# CarteTxCapteurDistance.net
KiCad netlist of a schematic drawn in Altium Designer
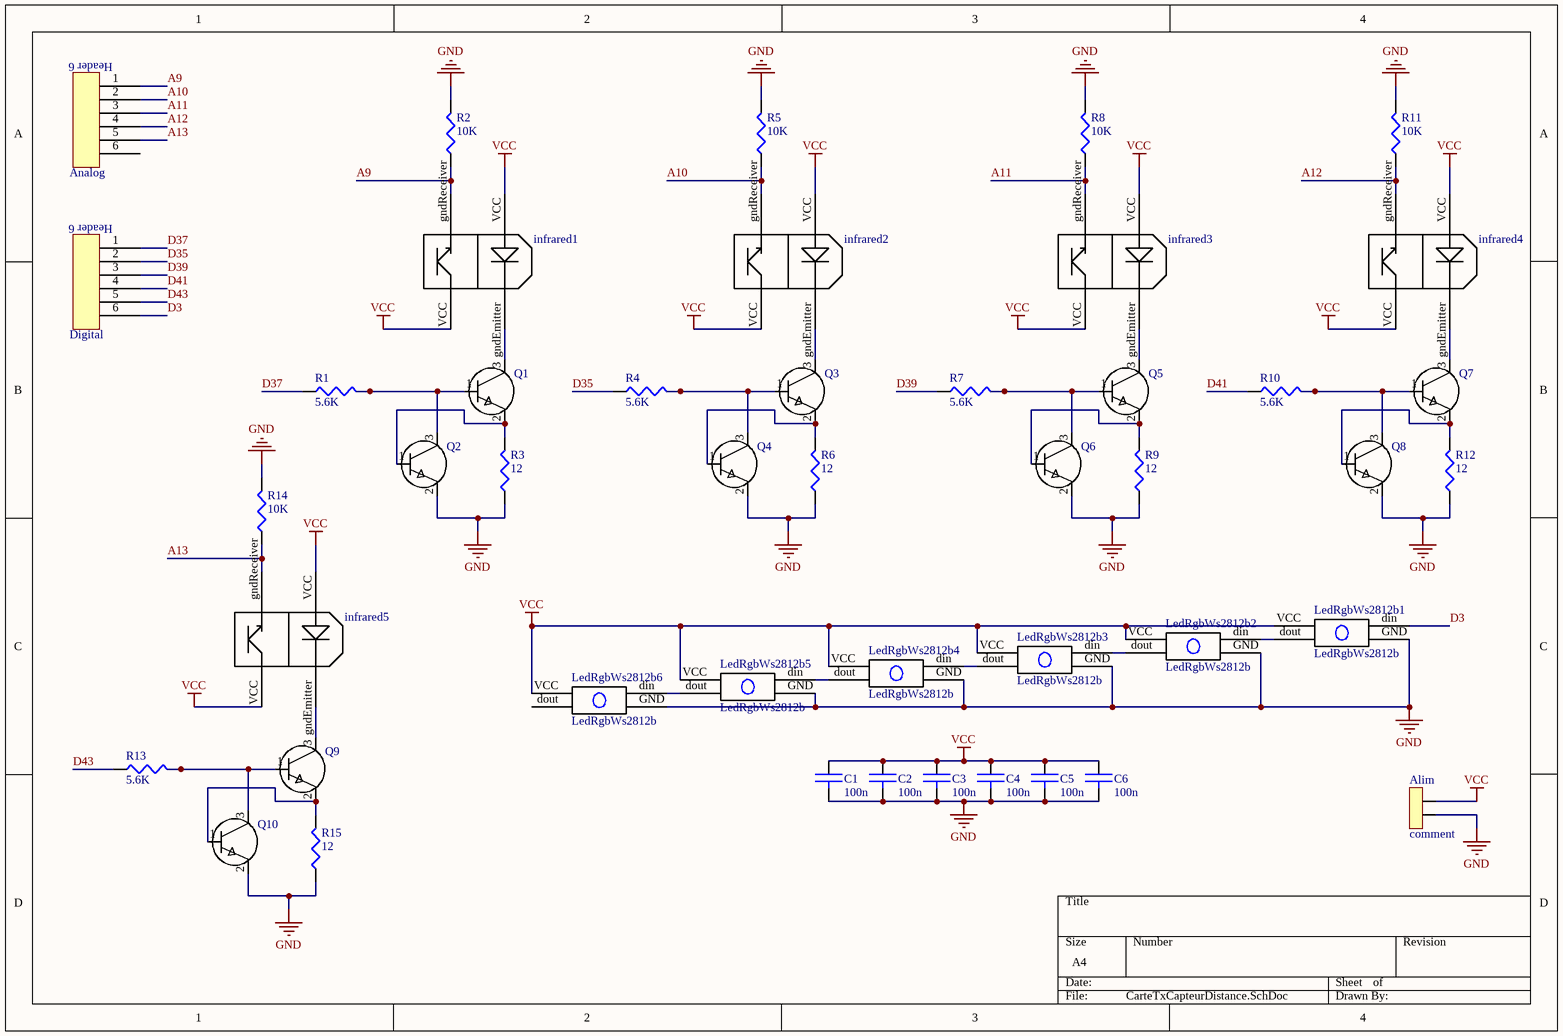
[diagram p0: CarteTxCapteurDistance.SchDoc]

(export (version "E")
  (design (tool "Eeschema 10.0.6"))
  (components
    (comp (ref "Alim")
      (value "comment")
      (footprint "POWER2")
      (description "connecteur alim 2 pôles")
      (libsource (lib "ISEN_basics_26-05-2015") (part "POWER2"))
    )
    (comp (ref "Analog")
      (value "Analog")
      (footprint "HEADER6")
      (libsource (lib "ledBitsLibrary") (part "HEADER6"))
    )
    (comp (ref "C1")
      (value "100n")
      (footprint "0805")
      (description "capacité non polarisée")
      (fields (field (name "Comment") "CAP"))
      (libsource (lib "ISEN_basics_26-05-2015") (part "CAP"))
    )
    (comp (ref "C2")
      (value "100n")
      (footprint "0805")
      (description "capacité non polarisée")
      (fields (field (name "Comment") "CAP"))
      (libsource (lib "ISEN_basics_26-05-2015") (part "CAP"))
    )
    (comp (ref "C3")
      (value "100n")
      (footprint "0805")
      (description "capacité non polarisée")
      (fields (field (name "Comment") "CAP"))
      (libsource (lib "ISEN_basics_26-05-2015") (part "CAP"))
    )
    (comp (ref "C4")
      (value "100n")
      (footprint "0805")
      (description "capacité non polarisée")
      (fields (field (name "Comment") "CAP"))
      (libsource (lib "ISEN_basics_26-05-2015") (part "CAP"))
    )
    (comp (ref "C5")
      (value "100n")
      (footprint "0805")
      (description "capacité non polarisée")
      (fields (field (name "Comment") "CAP"))
      (libsource (lib "ISEN_basics_26-05-2015") (part "CAP"))
    )
    (comp (ref "C6")
      (value "100n")
      (footprint "0805")
      (description "capacité non polarisée")
      (fields (field (name "Comment") "CAP"))
      (libsource (lib "ISEN_basics_26-05-2015") (part "CAP"))
    )
    (comp (ref "Digital")
      (value "Digital")
      (footprint "HEADER6")
      (libsource (lib "ledBitsLibrary") (part "HEADER6"))
    )
    (comp (ref "infrared1")
      (value "infrared")
      (footprint "Infrared")
      (libsource (lib "SecondLibrary") (part "RPR-359F"))
    )
    (comp (ref "infrared2")
      (value "infrared")
      (footprint "Infrared")
      (libsource (lib "SecondLibrary") (part "RPR-359F"))
    )
    (comp (ref "infrared3")
      (value "infrared")
      (footprint "Infrared")
      (libsource (lib "SecondLibrary") (part "RPR-359F"))
    )
    (comp (ref "infrared4")
      (value "infrared")
      (footprint "Infrared")
      (libsource (lib "SecondLibrary") (part "RPR-359F"))
    )
    (comp (ref "infrared5")
      (value "infrared")
      (footprint "Infrared")
      (libsource (lib "SecondLibrary") (part "RPR-359F"))
    )
    (comp (ref "LedRgbWs2812b1")
      (value "LedRgbWs2812b")
      (footprint "LedRgbWs2812b")
      (libsource (lib "SecondLibrary") (part "LedRgbWs2812b"))
    )
    (comp (ref "LedRgbWs2812b2")
      (value "LedRgbWs2812b")
      (footprint "LedRgbWs2812b")
      (libsource (lib "SecondLibrary") (part "LedRgbWs2812b"))
    )
    (comp (ref "LedRgbWs2812b3")
      (value "LedRgbWs2812b")
      (footprint "LedRgbWs2812b")
      (libsource (lib "SecondLibrary") (part "LedRgbWs2812b"))
    )
    (comp (ref "LedRgbWs2812b4")
      (value "LedRgbWs2812b")
      (footprint "LedRgbWs2812b")
      (libsource (lib "SecondLibrary") (part "LedRgbWs2812b"))
    )
    (comp (ref "LedRgbWs2812b5")
      (value "LedRgbWs2812b")
      (footprint "LedRgbWs2812b")
      (libsource (lib "SecondLibrary") (part "LedRgbWs2812b"))
    )
    (comp (ref "LedRgbWs2812b6")
      (value "LedRgbWs2812b")
      (footprint "LedRgbWs2812b")
      (libsource (lib "SecondLibrary") (part "LedRgbWs2812b"))
    )
    (comp (ref "Q1")
      (value "Q1")
      (footprint "BC817-40")
      (libsource (lib "SecondLibrary") (part "Transistors"))
    )
    (comp (ref "Q2")
      (value "Q2")
      (footprint "BC817-40")
      (libsource (lib "SecondLibrary") (part "Transistors"))
    )
    (comp (ref "Q3")
      (value "Q1")
      (footprint "BC817-40")
      (libsource (lib "SecondLibrary") (part "Transistors"))
    )
    (comp (ref "Q4")
      (value "Q2")
      (footprint "BC817-40")
      (libsource (lib "SecondLibrary") (part "Transistors"))
    )
    (comp (ref "Q5")
      (value "Q1")
      (footprint "BC817-40")
      (libsource (lib "SecondLibrary") (part "Transistors"))
    )
    (comp (ref "Q6")
      (value "Q2")
      (footprint "BC817-40")
      (libsource (lib "SecondLibrary") (part "Transistors"))
    )
    (comp (ref "Q7")
      (value "Q1")
      (footprint "BC817-40")
      (libsource (lib "SecondLibrary") (part "Transistors"))
    )
    (comp (ref "Q8")
      (value "Q2")
      (footprint "BC817-40")
      (libsource (lib "SecondLibrary") (part "Transistors"))
    )
    (comp (ref "Q9")
      (value "Q1")
      (footprint "BC817-40")
      (libsource (lib "SecondLibrary") (part "Transistors"))
    )
    (comp (ref "Q10")
      (value "Q2")
      (footprint "BC817-40")
      (libsource (lib "SecondLibrary") (part "Transistors"))
    )
    (comp (ref "R1")
      (value "5.6K")
      (footprint "0805")
      (description "resistance")
      (fields (field (name "Comment") "RES"))
      (libsource (lib "ISEN_basics_26-05-2015") (part "RES"))
    )
    (comp (ref "R2")
      (value "10K")
      (footprint "0805")
      (description "resistance")
      (fields (field (name "Comment") "RES"))
      (libsource (lib "ISEN_basics_26-05-2015") (part "RES"))
    )
    (comp (ref "R3")
      (value "12")
      (footprint "0805")
      (description "resistance")
      (fields (field (name "Comment") "RES"))
      (libsource (lib "ISEN_basics_26-05-2015") (part "RES"))
    )
    (comp (ref "R4")
      (value "5.6K")
      (footprint "0805")
      (description "resistance")
      (fields (field (name "Comment") "RES"))
      (libsource (lib "ISEN_basics_26-05-2015") (part "RES"))
    )
    (comp (ref "R5")
      (value "10K")
      (footprint "0805")
      (description "resistance")
      (fields (field (name "Comment") "RES"))
      (libsource (lib "ISEN_basics_26-05-2015") (part "RES"))
    )
    (comp (ref "R6")
      (value "12")
      (footprint "0805")
      (description "resistance")
      (fields (field (name "Comment") "RES"))
      (libsource (lib "ISEN_basics_26-05-2015") (part "RES"))
    )
    (comp (ref "R7")
      (value "5.6K")
      (footprint "0805")
      (description "resistance")
      (fields (field (name "Comment") "RES"))
      (libsource (lib "ISEN_basics_26-05-2015") (part "RES"))
    )
    (comp (ref "R8")
      (value "10K")
      (footprint "0805")
      (description "resistance")
      (fields (field (name "Comment") "RES"))
      (libsource (lib "ISEN_basics_26-05-2015") (part "RES"))
    )
    (comp (ref "R9")
      (value "12")
      (footprint "0805")
      (description "resistance")
      (fields (field (name "Comment") "RES"))
      (libsource (lib "ISEN_basics_26-05-2015") (part "RES"))
    )
    (comp (ref "R10")
      (value "5.6K")
      (footprint "0805")
      (description "resistance")
      (fields (field (name "Comment") "RES"))
      (libsource (lib "ISEN_basics_26-05-2015") (part "RES"))
    )
    (comp (ref "R11")
      (value "10K")
      (footprint "0805")
      (description "resistance")
      (fields (field (name "Comment") "RES"))
      (libsource (lib "ISEN_basics_26-05-2015") (part "RES"))
    )
    (comp (ref "R12")
      (value "12")
      (footprint "0805")
      (description "resistance")
      (fields (field (name "Comment") "RES"))
      (libsource (lib "ISEN_basics_26-05-2015") (part "RES"))
    )
    (comp (ref "R13")
      (value "5.6K")
      (footprint "0805")
      (description "resistance")
      (fields (field (name "Comment") "RES"))
      (libsource (lib "ISEN_basics_26-05-2015") (part "RES"))
    )
    (comp (ref "R14")
      (value "10K")
      (footprint "0805")
      (description "resistance")
      (fields (field (name "Comment") "RES"))
      (libsource (lib "ISEN_basics_26-05-2015") (part "RES"))
    )
    (comp (ref "R15")
      (value "12")
      (footprint "0805")
      (description "resistance")
      (fields (field (name "Comment") "RES"))
      (libsource (lib "ISEN_basics_26-05-2015") (part "RES"))
    )
  )
  (nets
    (net (code "1") (name "/A9") (class "Default")
      (node (ref "Analog") (pin "1") (pinfunction "1_1") (pintype "passive"))
      (node (ref "R2") (pin "1") (pintype "passive"))
      (node (ref "infrared1") (pin "gndReceiver") (pinfunction "gndReceiver_gndReceiver") (pintype "passive"))
    )
    (net (code "2") (name "/A10") (class "Default")
      (node (ref "Analog") (pin "2") (pinfunction "2_2") (pintype "passive"))
      (node (ref "R5") (pin "1") (pintype "passive"))
      (node (ref "infrared2") (pin "gndReceiver") (pinfunction "gndReceiver_gndReceiver") (pintype "passive"))
    )
    (net (code "3") (name "/A11") (class "Default")
      (node (ref "Analog") (pin "3") (pinfunction "3_3") (pintype "passive"))
      (node (ref "R8") (pin "1") (pintype "passive"))
      (node (ref "infrared3") (pin "gndReceiver") (pinfunction "gndReceiver_gndReceiver") (pintype "passive"))
    )
    (net (code "4") (name "/A12") (class "Default")
      (node (ref "Analog") (pin "4") (pinfunction "4_4") (pintype "passive"))
      (node (ref "R11") (pin "1") (pintype "passive"))
      (node (ref "infrared4") (pin "gndReceiver") (pinfunction "gndReceiver_gndReceiver") (pintype "passive"))
    )
    (net (code "5") (name "/A13") (class "Default")
      (node (ref "Analog") (pin "5") (pinfunction "5_5") (pintype "passive"))
      (node (ref "R14") (pin "1") (pintype "passive"))
      (node (ref "infrared5") (pin "gndReceiver") (pinfunction "gndReceiver_gndReceiver") (pintype "passive"))
    )
    (net (code "6") (name "/D3") (class "Default")
      (node (ref "Digital") (pin "6") (pinfunction "6_6") (pintype "passive"))
      (node (ref "LedRgbWs2812b1") (pin "din") (pinfunction "din_din") (pintype "passive"))
    )
    (net (code "7") (name "/D35") (class "Default")
      (node (ref "Digital") (pin "2") (pinfunction "2_2") (pintype "passive"))
      (node (ref "R4") (pin "1") (pintype "passive"))
    )
    (net (code "8") (name "/D37") (class "Default")
      (node (ref "Digital") (pin "1") (pinfunction "1_1") (pintype "passive"))
      (node (ref "R1") (pin "1") (pintype "passive"))
    )
    (net (code "9") (name "/D39") (class "Default")
      (node (ref "Digital") (pin "3") (pinfunction "3_3") (pintype "passive"))
      (node (ref "R7") (pin "1") (pintype "passive"))
    )
    (net (code "10") (name "/D41") (class "Default")
      (node (ref "Digital") (pin "4") (pinfunction "4_4") (pintype "passive"))
      (node (ref "R10") (pin "1") (pintype "passive"))
    )
    (net (code "11") (name "/D43") (class "Default")
      (node (ref "Digital") (pin "5") (pinfunction "5_5") (pintype "passive"))
      (node (ref "R13") (pin "1") (pintype "passive"))
    )
    (net (code "12") (name "GND") (class "Default")
      (node (ref "Alim") (pin "2") (pintype "passive"))
      (node (ref "C1") (pin "2") (pinfunction "2_2") (pintype "passive"))
      (node (ref "C2") (pin "2") (pinfunction "2_2") (pintype "passive"))
      (node (ref "C3") (pin "2") (pinfunction "2_2") (pintype "passive"))
      (node (ref "C4") (pin "2") (pinfunction "2_2") (pintype "passive"))
      (node (ref "C5") (pin "2") (pinfunction "2_2") (pintype "passive"))
      (node (ref "C6") (pin "2") (pinfunction "2_2") (pintype "passive"))
      (node (ref "LedRgbWs2812b1") (pin "GND") (pinfunction "GND_GND") (pintype "passive"))
      (node (ref "LedRgbWs2812b2") (pin "GND") (pinfunction "GND_GND") (pintype "passive"))
      (node (ref "LedRgbWs2812b3") (pin "GND") (pinfunction "GND_GND") (pintype "passive"))
      (node (ref "LedRgbWs2812b4") (pin "GND") (pinfunction "GND_GND") (pintype "passive"))
      (node (ref "LedRgbWs2812b5") (pin "GND") (pinfunction "GND_GND") (pintype "passive"))
      (node (ref "LedRgbWs2812b6") (pin "GND") (pinfunction "GND_GND") (pintype "passive"))
      (node (ref "Q10") (pin "2") (pinfunction "Emi_2") (pintype "passive"))
      (node (ref "Q2") (pin "2") (pinfunction "Emi_2") (pintype "passive"))
      (node (ref "Q4") (pin "2") (pinfunction "Emi_2") (pintype "passive"))
      (node (ref "Q6") (pin "2") (pinfunction "Emi_2") (pintype "passive"))
      (node (ref "Q8") (pin "2") (pinfunction "Emi_2") (pintype "passive"))
      (node (ref "R11") (pin "2") (pintype "passive"))
      (node (ref "R12") (pin "1") (pintype "passive"))
      (node (ref "R14") (pin "2") (pintype "passive"))
      (node (ref "R15") (pin "1") (pintype "passive"))
      (node (ref "R2") (pin "2") (pintype "passive"))
      (node (ref "R3") (pin "1") (pintype "passive"))
      (node (ref "R5") (pin "2") (pintype "passive"))
      (node (ref "R6") (pin "1") (pintype "passive"))
      (node (ref "R8") (pin "2") (pintype "passive"))
      (node (ref "R9") (pin "1") (pintype "passive"))
    )
    (net (code "13") (name "Net-(LedRgbWs2812b1-Paddout)") (class "Default")
      (node (ref "LedRgbWs2812b1") (pin "dout") (pinfunction "dout_dout") (pintype "passive"))
      (node (ref "LedRgbWs2812b2") (pin "din") (pinfunction "din_din") (pintype "passive"))
    )
    (net (code "14") (name "Net-(LedRgbWs2812b2-Paddout)") (class "Default")
      (node (ref "LedRgbWs2812b2") (pin "dout") (pinfunction "dout_dout") (pintype "passive"))
      (node (ref "LedRgbWs2812b3") (pin "din") (pinfunction "din_din") (pintype "passive"))
    )
    (net (code "15") (name "Net-(LedRgbWs2812b3-Paddout)") (class "Default")
      (node (ref "LedRgbWs2812b3") (pin "dout") (pinfunction "dout_dout") (pintype "passive"))
      (node (ref "LedRgbWs2812b4") (pin "din") (pinfunction "din_din") (pintype "passive"))
    )
    (net (code "16") (name "Net-(LedRgbWs2812b4-Paddout)") (class "Default")
      (node (ref "LedRgbWs2812b4") (pin "dout") (pinfunction "dout_dout") (pintype "passive"))
      (node (ref "LedRgbWs2812b5") (pin "din") (pinfunction "din_din") (pintype "passive"))
    )
    (net (code "17") (name "Net-(LedRgbWs2812b5-Paddout)") (class "Default")
      (node (ref "LedRgbWs2812b5") (pin "dout") (pinfunction "dout_dout") (pintype "passive"))
      (node (ref "LedRgbWs2812b6") (pin "din") (pinfunction "din_din") (pintype "passive"))
    )
    (net (code "18") (name "Net-(Q1-Base)") (class "Default")
      (node (ref "Q1") (pin "1") (pinfunction "Base_1") (pintype "passive"))
      (node (ref "Q2") (pin "3") (pinfunction "Co_3") (pintype "passive"))
      (node (ref "R1") (pin "2") (pintype "passive"))
    )
    (net (code "19") (name "Net-(Q1-Co)") (class "Default")
      (node (ref "Q1") (pin "3") (pinfunction "Co_3") (pintype "passive"))
      (node (ref "infrared1") (pin "gndEmitter") (pinfunction "gndEmitter_gndEmitter") (pintype "passive"))
    )
    (net (code "20") (name "Net-(Q1-Emi)") (class "Default")
      (node (ref "Q1") (pin "2") (pinfunction "Emi_2") (pintype "passive"))
      (node (ref "Q2") (pin "1") (pinfunction "Base_1") (pintype "passive"))
      (node (ref "R3") (pin "2") (pintype "passive"))
    )
    (net (code "21") (name "Net-(Q3-Base)") (class "Default")
      (node (ref "Q3") (pin "1") (pinfunction "Base_1") (pintype "passive"))
      (node (ref "Q4") (pin "3") (pinfunction "Co_3") (pintype "passive"))
      (node (ref "R4") (pin "2") (pintype "passive"))
    )
    (net (code "22") (name "Net-(Q3-Co)") (class "Default")
      (node (ref "Q3") (pin "3") (pinfunction "Co_3") (pintype "passive"))
      (node (ref "infrared2") (pin "gndEmitter") (pinfunction "gndEmitter_gndEmitter") (pintype "passive"))
    )
    (net (code "23") (name "Net-(Q3-Emi)") (class "Default")
      (node (ref "Q3") (pin "2") (pinfunction "Emi_2") (pintype "passive"))
      (node (ref "Q4") (pin "1") (pinfunction "Base_1") (pintype "passive"))
      (node (ref "R6") (pin "2") (pintype "passive"))
    )
    (net (code "24") (name "Net-(Q5-Base)") (class "Default")
      (node (ref "Q5") (pin "1") (pinfunction "Base_1") (pintype "passive"))
      (node (ref "Q6") (pin "3") (pinfunction "Co_3") (pintype "passive"))
      (node (ref "R7") (pin "2") (pintype "passive"))
    )
    (net (code "25") (name "Net-(Q5-Co)") (class "Default")
      (node (ref "Q5") (pin "3") (pinfunction "Co_3") (pintype "passive"))
      (node (ref "infrared3") (pin "gndEmitter") (pinfunction "gndEmitter_gndEmitter") (pintype "passive"))
    )
    (net (code "26") (name "Net-(Q5-Emi)") (class "Default")
      (node (ref "Q5") (pin "2") (pinfunction "Emi_2") (pintype "passive"))
      (node (ref "Q6") (pin "1") (pinfunction "Base_1") (pintype "passive"))
      (node (ref "R9") (pin "2") (pintype "passive"))
    )
    (net (code "27") (name "Net-(Q7-Base)") (class "Default")
      (node (ref "Q7") (pin "1") (pinfunction "Base_1") (pintype "passive"))
      (node (ref "Q8") (pin "3") (pinfunction "Co_3") (pintype "passive"))
      (node (ref "R10") (pin "2") (pintype "passive"))
    )
    (net (code "28") (name "Net-(Q7-Co)") (class "Default")
      (node (ref "Q7") (pin "3") (pinfunction "Co_3") (pintype "passive"))
      (node (ref "infrared4") (pin "gndEmitter") (pinfunction "gndEmitter_gndEmitter") (pintype "passive"))
    )
    (net (code "29") (name "Net-(Q7-Emi)") (class "Default")
      (node (ref "Q7") (pin "2") (pinfunction "Emi_2") (pintype "passive"))
      (node (ref "Q8") (pin "1") (pinfunction "Base_1") (pintype "passive"))
      (node (ref "R12") (pin "2") (pintype "passive"))
    )
    (net (code "30") (name "Net-(Q9-Co)") (class "Default")
      (node (ref "Q9") (pin "3") (pinfunction "Co_3") (pintype "passive"))
      (node (ref "infrared5") (pin "gndEmitter") (pinfunction "gndEmitter_gndEmitter") (pintype "passive"))
    )
    (net (code "31") (name "Net-(Q10-Base)") (class "Default")
      (node (ref "Q10") (pin "1") (pinfunction "Base_1") (pintype "passive"))
      (node (ref "Q9") (pin "2") (pinfunction "Emi_2") (pintype "passive"))
      (node (ref "R15") (pin "2") (pintype "passive"))
    )
    (net (code "32") (name "Net-(Q10-Co)") (class "Default")
      (node (ref "Q10") (pin "3") (pinfunction "Co_3") (pintype "passive"))
      (node (ref "Q9") (pin "1") (pinfunction "Base_1") (pintype "passive"))
      (node (ref "R13") (pin "2") (pintype "passive"))
    )
    (net (code "33") (name "VCC") (class "Default")
      (node (ref "Alim") (pin "1") (pintype "passive"))
      (node (ref "C1") (pin "1") (pinfunction "1_1") (pintype "passive"))
      (node (ref "C2") (pin "1") (pinfunction "1_1") (pintype "passive"))
      (node (ref "C3") (pin "1") (pinfunction "1_1") (pintype "passive"))
      (node (ref "C4") (pin "1") (pinfunction "1_1") (pintype "passive"))
      (node (ref "C5") (pin "1") (pinfunction "1_1") (pintype "passive"))
      (node (ref "C6") (pin "1") (pinfunction "1_1") (pintype "passive"))
      (node (ref "LedRgbWs2812b1") (pin "VCC") (pinfunction "VCC_VCC") (pintype "passive"))
      (node (ref "LedRgbWs2812b2") (pin "VCC") (pinfunction "VCC_VCC") (pintype "passive"))
      (node (ref "LedRgbWs2812b3") (pin "VCC") (pinfunction "VCC_VCC") (pintype "passive"))
      (node (ref "LedRgbWs2812b4") (pin "VCC") (pinfunction "VCC_VCC") (pintype "passive"))
      (node (ref "LedRgbWs2812b5") (pin "VCC") (pinfunction "VCC_VCC") (pintype "passive"))
      (node (ref "LedRgbWs2812b6") (pin "VCC") (pinfunction "VCC_VCC") (pintype "passive"))
      (node (ref "infrared1") (pin "VCC") (pinfunction "VCC_VCC") (pintype "passive"))
      (node (ref "infrared2") (pin "VCC") (pinfunction "VCC_VCC") (pintype "passive"))
      (node (ref "infrared3") (pin "VCC") (pinfunction "VCC_VCC") (pintype "passive"))
      (node (ref "infrared4") (pin "VCC") (pinfunction "VCC_VCC") (pintype "passive"))
      (node (ref "infrared5") (pin "VCC") (pinfunction "VCC_VCC") (pintype "passive"))
    )
    (net (code "34") (name "unconnected-(Analog-Pad6)") (class "Default")
      (node (ref "Analog") (pin "6") (pinfunction "6_6") (pintype "passive"))
    )
    (net (code "35") (name "unconnected-(LedRgbWs2812b6-Paddout)") (class "Default")
      (node (ref "LedRgbWs2812b6") (pin "dout") (pinfunction "dout_dout") (pintype "passive"))
    )
  )
)
